# headers_botones.net
KiCad netlist of a schematic drawn in Altium Designer
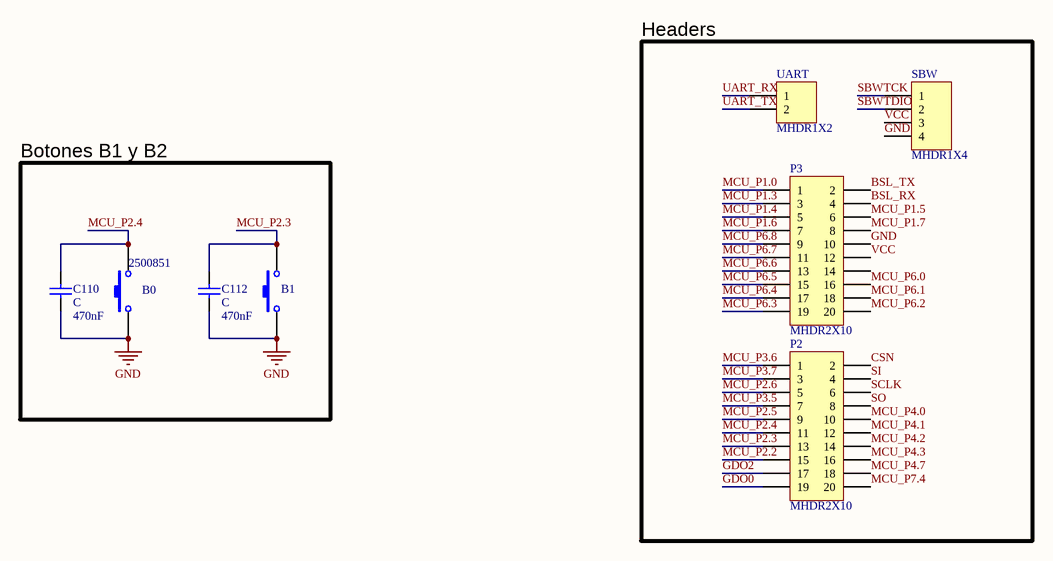
[diagram p0: headers_botones.SchDoc]

(export (version "E")
  (design (tool "Eeschema 10.0.6"))
  (components
    (comp (ref "B0")
      (value "Pulsador")
      (footprint "PushButton")
      (description "Switch")
      (fields
        (field (name "MANUFACTURER") "Generic Components")
        (field (name "SUPPLIER PART NUMBER 1") "2500851")
      )
      (libsource (lib "LSI") (part "Pulsador_1"))
    )
    (comp (ref "B1")
      (value "Pulsador")
      (footprint "pushbutton")
      (description "Switch")
      (fields (field (name "MANUFACTURER") "Generic Components"))
      (libsource (lib "LSI") (part "Pulsador_1"))
    )
    (comp (ref "C110")
      (value "C")
      (footprint "0805 CAP")
      (description "Capacitor")
      (fields
        (field (name "MANUFACTURER") "Generic Components")
        (field (name "ALTIUM_VALUE") "470nF")
        (field (name "PUBLISHER") "Altium Hobart Technology Centre")
      )
      (libsource (lib "LSI") (part "C"))
    )
    (comp (ref "C112")
      (value "C")
      (footprint "0805 CAP")
      (description "Capacitor")
      (fields
        (field (name "MANUFACTURER") "Generic Components")
        (field (name "ALTIUM_VALUE") "470nF")
        (field (name "PUBLISHER") "Altium Hobart Technology Centre")
      )
      (libsource (lib "LSI") (part "C"))
    )
    (comp (ref "P2")
      (value "MHDR2X10")
      (footprint "HDR2X10")
      (description "Header, 10-Pin, Dual row")
      (fields (field (name "PUBLISHER") "Altium Limited"))
      (libsource (lib "Miscellaneous Connectors") (part "MHDR2X10"))
    )
    (comp (ref "P3")
      (value "MHDR2X10")
      (footprint "HDR2X10")
      (description "Header, 10-Pin, Dual row")
      (fields (field (name "PUBLISHER") "Altium Limited"))
      (libsource (lib "Miscellaneous Connectors") (part "MHDR2X10"))
    )
    (comp (ref "SBW")
      (value "MHDR1X4")
      (footprint "HDR1X4")
      (description "Header, 4-Pin")
      (fields (field (name "PUBLISHER") "Altium Limited"))
      (libsource (lib "Miscellaneous Connectors") (part "MHDR1X4"))
    )
    (comp (ref "UART")
      (value "MHDR1X2")
      (footprint "HDR1X2")
      (description "Header, 2-Pin")
      (fields (field (name "PUBLISHER") "Altium Limited"))
      (libsource (lib "Miscellaneous Connectors") (part "MHDR1X2"))
    )
  )
  (nets
    (net (code "1") (name "/BSL_RX") (class "Default")
      (node (ref "P3") (pin "4") (pinfunction "4_4") (pintype "passive"))
    )
    (net (code "2") (name "/BSL_TX") (class "Default")
      (node (ref "P3") (pin "2") (pinfunction "2_2") (pintype "passive"))
    )
    (net (code "3") (name "/CSN") (class "Default")
      (node (ref "P2") (pin "2") (pinfunction "2_2") (pintype "passive"))
    )
    (net (code "4") (name "/GDO0") (class "Default")
      (node (ref "P2") (pin "19") (pinfunction "19_19") (pintype "passive"))
    )
    (net (code "5") (name "/GDO2") (class "Default")
      (node (ref "P2") (pin "17") (pinfunction "17_17") (pintype "passive"))
    )
    (net (code "6") (name "/MCU_P1.0") (class "Default")
      (node (ref "P3") (pin "1") (pinfunction "1_1") (pintype "passive"))
    )
    (net (code "7") (name "/MCU_P1.3") (class "Default")
      (node (ref "P3") (pin "3") (pinfunction "3_3") (pintype "passive"))
    )
    (net (code "8") (name "/MCU_P1.4") (class "Default")
      (node (ref "P3") (pin "5") (pinfunction "5_5") (pintype "passive"))
    )
    (net (code "9") (name "/MCU_P1.5") (class "Default")
      (node (ref "P3") (pin "6") (pinfunction "6_6") (pintype "passive"))
    )
    (net (code "10") (name "/MCU_P1.6") (class "Default")
      (node (ref "P3") (pin "7") (pinfunction "7_7") (pintype "passive"))
    )
    (net (code "11") (name "/MCU_P1.7") (class "Default")
      (node (ref "P3") (pin "8") (pinfunction "8_8") (pintype "passive"))
    )
    (net (code "12") (name "/MCU_P2.2") (class "Default")
      (node (ref "P2") (pin "15") (pinfunction "15_15") (pintype "passive"))
    )
    (net (code "13") (name "/MCU_P2.3") (class "Default")
      (node (ref "B1") (pin "2") (pinfunction "2_2") (pintype "passive"))
      (node (ref "C112") (pin "2") (pinfunction "2_2") (pintype "passive"))
      (node (ref "P2") (pin "13") (pinfunction "13_13") (pintype "passive"))
    )
    (net (code "14") (name "/MCU_P2.4") (class "Default")
      (node (ref "B0") (pin "2") (pinfunction "2_2") (pintype "passive"))
      (node (ref "C110") (pin "2") (pinfunction "2_2") (pintype "passive"))
      (node (ref "P2") (pin "11") (pinfunction "11_11") (pintype "passive"))
    )
    (net (code "15") (name "/MCU_P2.5") (class "Default")
      (node (ref "P2") (pin "9") (pinfunction "9_9") (pintype "passive"))
    )
    (net (code "16") (name "/MCU_P2.6") (class "Default")
      (node (ref "P2") (pin "5") (pinfunction "5_5") (pintype "passive"))
    )
    (net (code "17") (name "/MCU_P3.5") (class "Default")
      (node (ref "P2") (pin "7") (pinfunction "7_7") (pintype "passive"))
    )
    (net (code "18") (name "/MCU_P3.6") (class "Default")
      (node (ref "P2") (pin "1") (pinfunction "1_1") (pintype "passive"))
    )
    (net (code "19") (name "/MCU_P3.7") (class "Default")
      (node (ref "P2") (pin "3") (pinfunction "3_3") (pintype "passive"))
    )
    (net (code "20") (name "/MCU_P4.0") (class "Default")
      (node (ref "P2") (pin "10") (pinfunction "10_10") (pintype "passive"))
    )
    (net (code "21") (name "/MCU_P4.1") (class "Default")
      (node (ref "P2") (pin "12") (pinfunction "12_12") (pintype "passive"))
    )
    (net (code "22") (name "/MCU_P4.2") (class "Default")
      (node (ref "P2") (pin "14") (pinfunction "14_14") (pintype "passive"))
    )
    (net (code "23") (name "/MCU_P4.3") (class "Default")
      (node (ref "P2") (pin "16") (pinfunction "16_16") (pintype "passive"))
    )
    (net (code "24") (name "/MCU_P4.7") (class "Default")
      (node (ref "P2") (pin "18") (pinfunction "18_18") (pintype "passive"))
    )
    (net (code "25") (name "/MCU_P6.0") (class "Default")
      (node (ref "P3") (pin "16") (pinfunction "16_16") (pintype "passive"))
    )
    (net (code "26") (name "/MCU_P6.1") (class "Default")
      (node (ref "P3") (pin "18") (pinfunction "18_18") (pintype "passive"))
    )
    (net (code "27") (name "/MCU_P6.2") (class "Default")
      (node (ref "P3") (pin "20") (pinfunction "20_20") (pintype "passive"))
    )
    (net (code "28") (name "/MCU_P6.3") (class "Default")
      (node (ref "P3") (pin "19") (pinfunction "19_19") (pintype "passive"))
    )
    (net (code "29") (name "/MCU_P6.4") (class "Default")
      (node (ref "P3") (pin "17") (pinfunction "17_17") (pintype "passive"))
    )
    (net (code "30") (name "/MCU_P6.5") (class "Default")
      (node (ref "P3") (pin "15") (pinfunction "15_15") (pintype "passive"))
    )
    (net (code "31") (name "/MCU_P6.6") (class "Default")
      (node (ref "P3") (pin "13") (pinfunction "13_13") (pintype "passive"))
    )
    (net (code "32") (name "/MCU_P6.7") (class "Default")
      (node (ref "P3") (pin "11") (pinfunction "11_11") (pintype "passive"))
    )
    (net (code "33") (name "/MCU_P6.8") (class "Default")
      (node (ref "P3") (pin "9") (pinfunction "9_9") (pintype "passive"))
    )
    (net (code "34") (name "/MCU_P7.4") (class "Default")
      (node (ref "P2") (pin "20") (pinfunction "20_20") (pintype "passive"))
    )
    (net (code "35") (name "/SBWTCK") (class "Default")
      (node (ref "SBW") (pin "1") (pinfunction "1_1") (pintype "passive"))
    )
    (net (code "36") (name "/SBWTDIO") (class "Default")
      (node (ref "SBW") (pin "2") (pinfunction "2_2") (pintype "passive"))
    )
    (net (code "37") (name "/SCLK") (class "Default")
      (node (ref "P2") (pin "6") (pinfunction "6_6") (pintype "passive"))
    )
    (net (code "38") (name "/SI") (class "Default")
      (node (ref "P2") (pin "4") (pinfunction "4_4") (pintype "passive"))
    )
    (net (code "39") (name "/SO") (class "Default")
      (node (ref "P2") (pin "8") (pinfunction "8_8") (pintype "passive"))
    )
    (net (code "40") (name "/UART_RX") (class "Default")
      (node (ref "UART") (pin "1") (pinfunction "1_1") (pintype "passive"))
    )
    (net (code "41") (name "/UART_TX") (class "Default")
      (node (ref "UART") (pin "2") (pinfunction "2_2") (pintype "passive"))
    )
    (net (code "42") (name "/VCC") (class "Default")
      (node (ref "P3") (pin "12") (pinfunction "12_12") (pintype "passive"))
      (node (ref "SBW") (pin "3") (pinfunction "3_3") (pintype "passive"))
    )
    (net (code "43") (name "GND") (class "Default")
      (node (ref "B0") (pin "1") (pinfunction "1_1") (pintype "passive"))
      (node (ref "B1") (pin "1") (pinfunction "1_1") (pintype "passive"))
      (node (ref "C110") (pin "1") (pinfunction "1_1") (pintype "passive"))
      (node (ref "C112") (pin "1") (pinfunction "1_1") (pintype "passive"))
      (node (ref "P3") (pin "10") (pinfunction "10_10") (pintype "passive"))
      (node (ref "SBW") (pin "4") (pinfunction "4_4") (pintype "passive"))
    )
    (net (code "44") (name "unconnected-(P3-Pad14)") (class "Default")
      (node (ref "P3") (pin "14") (pinfunction "14_14") (pintype "passive"))
    )
  )
)
